# LVDS_IFC_MCX.net
KiCad netlist of a schematic drawn in Altium Designer
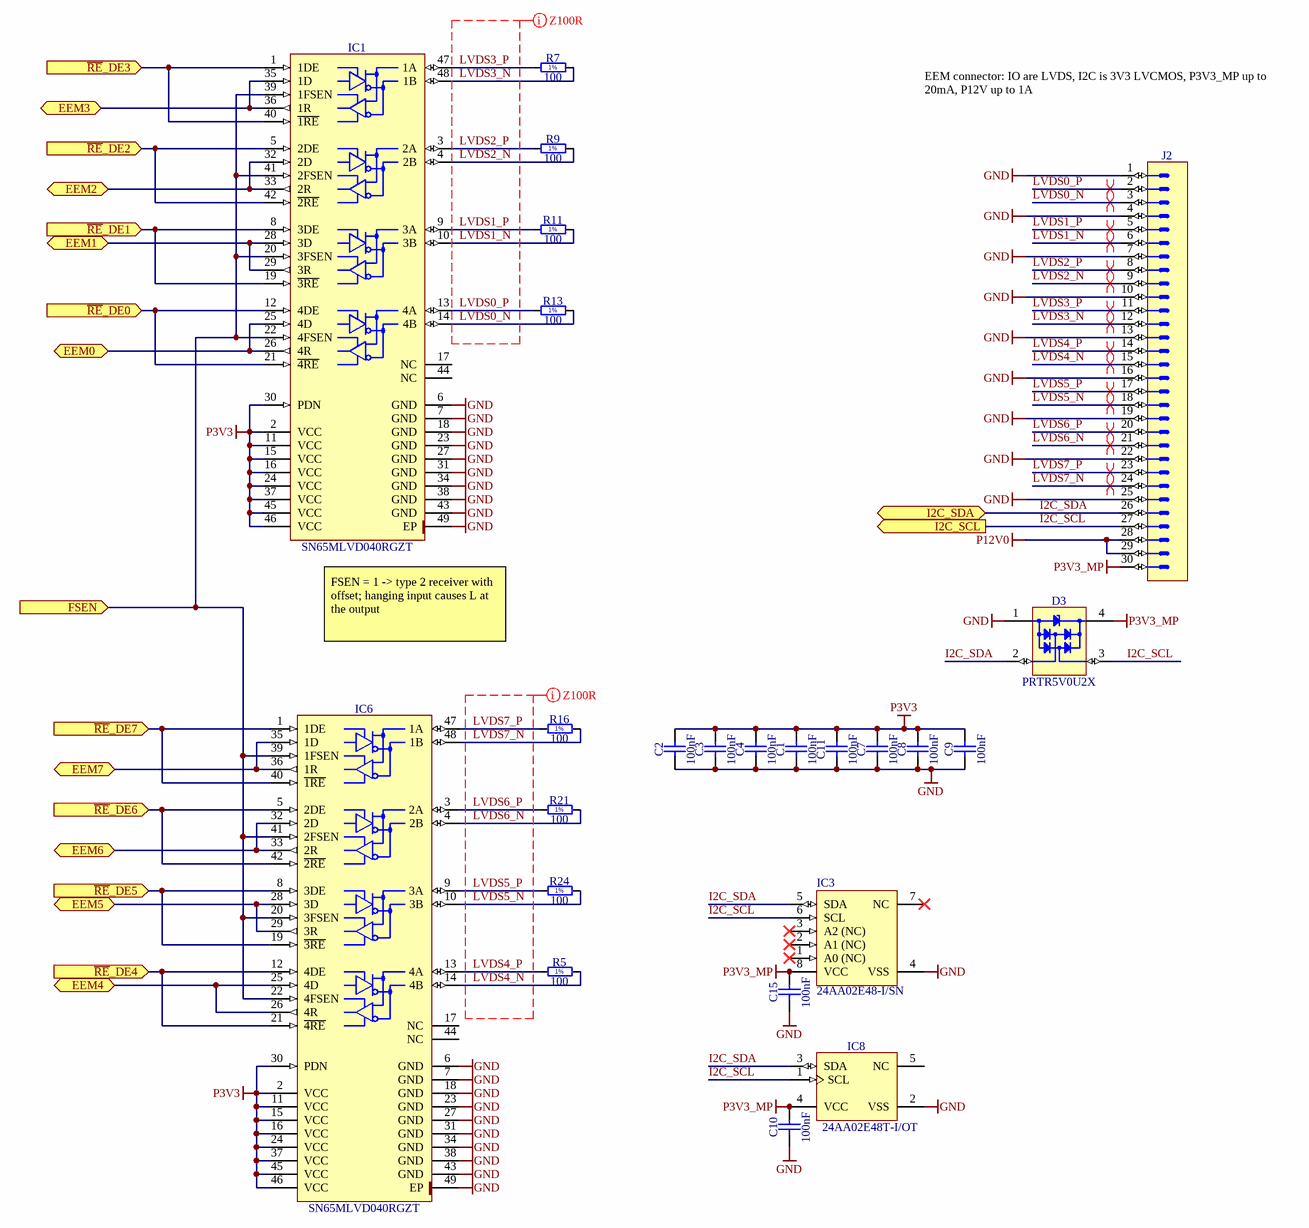
[diagram p0: LVDS_IFC_MCX.SchDoc]

(export (version "E")
  (design (tool "Eeschema 10.0.6"))
  (components
    (comp (ref "C1")
      (value "100nF")
      (footprint "CAPC1005X55N")
      (description "Non-polarised capacitor")
      (fields
        (field (name "PART NUMBER") "CC0402_100NF_16V_10%_X5R")
        (field (name "VOLTAGE") "16V")
        (field (name "AUTHOR") "CERN DEM JLC")
      )
      (libsource (lib "Capacitors") (part "Capacitor - non polarized"))
    )
    (comp (ref "C2")
      (value "100nF")
      (footprint "CAPC1005X55N")
      (description "Non-polarised capacitor")
      (fields
        (field (name "PART NUMBER") "CC0402_100NF_16V_10%_X5R")
        (field (name "VOLTAGE") "16V")
        (field (name "AUTHOR") "CERN DEM JLC")
      )
      (libsource (lib "Capacitors") (part "Capacitor - non polarized"))
    )
    (comp (ref "C3")
      (value "100nF")
      (footprint "CAPC1005X55N")
      (description "Non-polarised capacitor")
      (fields
        (field (name "PART NUMBER") "CC0402_100NF_16V_10%_X5R")
        (field (name "VOLTAGE") "16V")
        (field (name "AUTHOR") "CERN DEM JLC")
      )
      (libsource (lib "Capacitors") (part "Capacitor - non polarized"))
    )
    (comp (ref "C4")
      (value "100nF")
      (footprint "CAPC1005X55N")
      (description "Non-polarised capacitor")
      (fields
        (field (name "PART NUMBER") "CC0402_100NF_16V_10%_X5R")
        (field (name "VOLTAGE") "16V")
        (field (name "AUTHOR") "CERN DEM JLC")
      )
      (libsource (lib "Capacitors") (part "Capacitor - non polarized"))
    )
    (comp (ref "C7")
      (value "100nF")
      (footprint "CAPC1005X55N")
      (description "Non-polarised capacitor")
      (fields
        (field (name "PART NUMBER") "CC0402_100NF_16V_10%_X5R")
        (field (name "VOLTAGE") "16V")
        (field (name "AUTHOR") "CERN DEM JLC")
      )
      (libsource (lib "Capacitors") (part "Capacitor - non polarized"))
    )
    (comp (ref "C8")
      (value "100nF")
      (footprint "CAPC1005X55N")
      (description "Non-polarised capacitor")
      (fields
        (field (name "PART NUMBER") "CC0402_100NF_16V_10%_X5R")
        (field (name "VOLTAGE") "16V")
        (field (name "AUTHOR") "CERN DEM JLC")
      )
      (libsource (lib "Capacitors") (part "Capacitor - non polarized"))
    )
    (comp (ref "C9")
      (value "100nF")
      (footprint "CAPC1005X55N")
      (description "Non-polarised capacitor")
      (fields
        (field (name "PART NUMBER") "CC0402_100NF_16V_10%_X5R")
        (field (name "VOLTAGE") "16V")
        (field (name "AUTHOR") "CERN DEM JLC")
      )
      (libsource (lib "Capacitors") (part "Capacitor - non polarized"))
    )
    (comp (ref "C10")
      (value "100nF")
      (footprint "CAPC1005X55N")
      (description "Non-polarised capacitor")
      (fields
        (field (name "PART NUMBER") "CC0402_100NF_16V_10%_X5R")
        (field (name "VOLTAGE") "16V")
        (field (name "AUTHOR") "CERN DEM JLC")
      )
      (libsource (lib "Capacitors") (part "Capacitor - non polarized"))
    )
    (comp (ref "C11")
      (value "100nF")
      (footprint "CAPC1005X55N")
      (description "Non-polarised capacitor")
      (fields
        (field (name "PART NUMBER") "CC0402_100NF_16V_10%_X5R")
        (field (name "VOLTAGE") "16V")
        (field (name "AUTHOR") "CERN DEM JLC")
      )
      (libsource (lib "Capacitors") (part "Capacitor - non polarized"))
    )
    (comp (ref "C15")
      (value "100nF")
      (footprint "CAPC1005X55N")
      (description "Non-polarised capacitor")
      (fields
        (field (name "PART NUMBER") "CC0402_100NF_16V_10%_X5R")
        (field (name "VOLTAGE") "16V")
        (field (name "AUTHOR") "CERN DEM JLC")
      )
      (libsource (lib "Capacitors") (part "Capacitor - non polarized"))
    )
    (comp (ref "D3")
      (value "PRTR5V0U2X")
      (footprint "SOT190P230X110-4N")
      (description "Ultra Low Capacitance Double Rail-to-Rail ESD Protection Diode")
      (fields
        (field (name "VOLTAGE") "5.5V")
        (field (name "MANUFACTURER") "NXP SEMICONDUCTORS")
        (field (name "AUTHOR") "CERN DEM JLC")
      )
      (libsource (lib "ICs And Semiconductors") (part "PRTR5V0U2X"))
    )
    (comp (ref "IC1")
      (value "SN65MLVD040RGZT")
      (footprint "QFN50P700X700X100-49N-S420")
      (description "4-Channel Half-Duplex M-LVDS Line Transceiver")
      (fields (field (name "MANUFACTURER") "TEXAS INSTRUMENTS") (field (name "AUTHOR") "CERN DEM JLC"))
      (libsource (lib "ICs And Semiconductors") (part "SN65MLVD040"))
    )
    (comp (ref "IC3")
      (value "24AA02E48-I/SN")
      (footprint "SOIC127")
      (description "1.7V-5.5V, 2K I2C™ Serial EEPROMs with EUI-48™ Node Identity")
      (libsource (lib "Integrated_Library_MP") (part "24AA02E48-I/SN"))
    )
    (comp (ref "IC6")
      (value "SN65MLVD040RGZT")
      (footprint "QFN50P700X700X100-49N-S420")
      (description "4-Channel Half-Duplex M-LVDS Line Transceiver")
      (fields (field (name "MANUFACTURER") "TEXAS INSTRUMENTS") (field (name "AUTHOR") "CERN DEM JLC"))
      (libsource (lib "ICs And Semiconductors") (part "SN65MLVD040"))
    )
    (comp (ref "IC8")
      (value "24AA02E48T-I/OT")
      (footprint "SOT95P280X145-5N")
      (description "1.7V-5.5V, 2K I2C Serial EEPROM With EUI-48 Node Identity")
      (fields (field (name "MANUFACTURER") "MICROCHIP TECHNOLOGY") (field (name "AUTHOR") "CERN DEM MR"))
      (libsource (lib "ICs And Semiconductors") (part "24AA02E48T-I/OT"))
    )
    (comp (ref "J2")
      (value "~")
      (footprint "3M_N2530-6002RB")
      (description "Connector 30 Male")
      (fields
        (field (name "PART NUMBER") "3M_N2530-6002RB")
        (field (name "MANUFACTURER") "3M")
        (field (name "AUTHOR") "CERN DEM JLC")
      )
      (libsource (lib "Connectors") (part "Connector 30 Male"))
    )
    (comp (ref "R5")
      (value "100")
      (footprint "RESC1005X40N")
      (description "Resistor - 1%")
      (fields
        (field (name "PART NUMBER") "R0402_100R_1%_0.1W_100PPM")
        (field (name "POWER") "0.1W")
        (field (name "AUTHOR") "CERN DEM JLC")
      )
      (libsource (lib "Resistors") (part "Resistor - 1%"))
    )
    (comp (ref "R7")
      (value "100")
      (footprint "RESC1005X40N")
      (description "Resistor - 1%")
      (fields
        (field (name "PART NUMBER") "R0402_100R_1%_0.1W_100PPM")
        (field (name "POWER") "0.1W")
        (field (name "AUTHOR") "CERN DEM JLC")
      )
      (libsource (lib "Resistors") (part "Resistor - 1%"))
    )
    (comp (ref "R9")
      (value "100")
      (footprint "RESC1005X40N")
      (description "Resistor - 1%")
      (fields
        (field (name "PART NUMBER") "R0402_100R_1%_0.1W_100PPM")
        (field (name "POWER") "0.1W")
        (field (name "AUTHOR") "CERN DEM JLC")
      )
      (libsource (lib "Resistors") (part "Resistor - 1%"))
    )
    (comp (ref "R11")
      (value "100")
      (footprint "RESC1005X40N")
      (description "Resistor - 1%")
      (fields
        (field (name "PART NUMBER") "R0402_100R_1%_0.1W_100PPM")
        (field (name "POWER") "0.1W")
        (field (name "AUTHOR") "CERN DEM JLC")
      )
      (libsource (lib "Resistors") (part "Resistor - 1%"))
    )
    (comp (ref "R13")
      (value "100")
      (footprint "RESC1005X40N")
      (description "Resistor - 1%")
      (fields
        (field (name "PART NUMBER") "R0402_100R_1%_0.1W_100PPM")
        (field (name "POWER") "0.1W")
        (field (name "AUTHOR") "CERN DEM JLC")
      )
      (libsource (lib "Resistors") (part "Resistor - 1%"))
    )
    (comp (ref "R16")
      (value "100")
      (footprint "RESC1005X40N")
      (description "Resistor - 1%")
      (fields
        (field (name "PART NUMBER") "R0402_100R_1%_0.1W_100PPM")
        (field (name "POWER") "0.1W")
        (field (name "AUTHOR") "CERN DEM JLC")
      )
      (libsource (lib "Resistors") (part "Resistor - 1%"))
    )
    (comp (ref "R21")
      (value "100")
      (footprint "RESC1005X40N")
      (description "Resistor - 1%")
      (fields
        (field (name "PART NUMBER") "R0402_100R_1%_0.1W_100PPM")
        (field (name "POWER") "0.1W")
        (field (name "AUTHOR") "CERN DEM JLC")
      )
      (libsource (lib "Resistors") (part "Resistor - 1%"))
    )
    (comp (ref "R24")
      (value "100")
      (footprint "RESC1005X40N")
      (description "Resistor - 1%")
      (fields
        (field (name "PART NUMBER") "R0402_100R_1%_0.1W_100PPM")
        (field (name "POWER") "0.1W")
        (field (name "AUTHOR") "CERN DEM JLC")
      )
      (libsource (lib "Resistors") (part "Resistor - 1%"))
    )
  )
  (nets
    (net (code "1") (name "/EEM0") (class "Default")
      (node (ref "IC1") (pin "25") (pinfunction "4D_25") (pintype "input"))
      (node (ref "IC1") (pin "26") (pinfunction "4R_26") (pintype "output"))
    )
    (net (code "2") (name "/EEM1") (class "Default")
      (node (ref "IC1") (pin "28") (pinfunction "3D_28") (pintype "input"))
      (node (ref "IC1") (pin "29") (pinfunction "3R_29") (pintype "output"))
    )
    (net (code "3") (name "/EEM2") (class "Default")
      (node (ref "IC1") (pin "32") (pinfunction "2D_32") (pintype "input"))
      (node (ref "IC1") (pin "33") (pinfunction "2R_33") (pintype "output"))
    )
    (net (code "4") (name "/EEM3") (class "Default")
      (node (ref "IC1") (pin "35") (pinfunction "1D_35") (pintype "input"))
      (node (ref "IC1") (pin "36") (pinfunction "1R_36") (pintype "output"))
    )
    (net (code "5") (name "/EEM4") (class "Default")
      (node (ref "IC6") (pin "25") (pinfunction "4D_25") (pintype "input"))
      (node (ref "IC6") (pin "26") (pinfunction "4R_26") (pintype "output"))
    )
    (net (code "6") (name "/EEM5") (class "Default")
      (node (ref "IC6") (pin "28") (pinfunction "3D_28") (pintype "input"))
      (node (ref "IC6") (pin "29") (pinfunction "3R_29") (pintype "output"))
    )
    (net (code "7") (name "/EEM6") (class "Default")
      (node (ref "IC6") (pin "32") (pinfunction "2D_32") (pintype "input"))
      (node (ref "IC6") (pin "33") (pinfunction "2R_33") (pintype "output"))
    )
    (net (code "8") (name "/EEM7") (class "Default")
      (node (ref "IC6") (pin "35") (pinfunction "1D_35") (pintype "input"))
      (node (ref "IC6") (pin "36") (pinfunction "1R_36") (pintype "output"))
    )
    (net (code "9") (name "/FSEN") (class "Default")
      (node (ref "IC1") (pin "20") (pinfunction "3FSEN_20") (pintype "input"))
      (node (ref "IC1") (pin "22") (pinfunction "4FSEN_22") (pintype "input"))
      (node (ref "IC1") (pin "39") (pinfunction "1FSEN_39") (pintype "input"))
      (node (ref "IC1") (pin "41") (pinfunction "2FSEN_41") (pintype "input"))
      (node (ref "IC6") (pin "20") (pinfunction "3FSEN_20") (pintype "input"))
      (node (ref "IC6") (pin "22") (pinfunction "4FSEN_22") (pintype "input"))
      (node (ref "IC6") (pin "39") (pinfunction "1FSEN_39") (pintype "input"))
      (node (ref "IC6") (pin "41") (pinfunction "2FSEN_41") (pintype "input"))
    )
    (net (code "10") (name "/I2C_SCL") (class "Default")
      (node (ref "D3") (pin "3") (pinfunction "I/O2_3") (pintype "bidirectional"))
      (node (ref "IC3") (pin "6") (pinfunction "SCL_6") (pintype "input"))
      (node (ref "IC8") (pin "1") (pinfunction "SCL_1") (pintype "input"))
      (node (ref "J2") (pin "27") (pinfunction "27_27") (pintype "bidirectional"))
    )
    (net (code "11") (name "/I2C_SDA") (class "Default")
      (node (ref "D3") (pin "2") (pinfunction "I/O1_2") (pintype "bidirectional"))
      (node (ref "IC3") (pin "5") (pinfunction "SDA_5") (pintype "bidirectional"))
      (node (ref "IC8") (pin "3") (pinfunction "SDA_3") (pintype "bidirectional"))
      (node (ref "J2") (pin "26") (pinfunction "26_26") (pintype "bidirectional"))
    )
    (net (code "12") (name "/LVDS0_N") (class "Default")
      (node (ref "IC1") (pin "14") (pinfunction "4B_14") (pintype "bidirectional"))
      (node (ref "J2") (pin "3") (pinfunction "3_3") (pintype "bidirectional"))
      (node (ref "R13") (pin "2") (pinfunction "2_2") (pintype "passive"))
    )
    (net (code "13") (name "/LVDS0_P") (class "Default")
      (node (ref "IC1") (pin "13") (pinfunction "4A_13") (pintype "bidirectional"))
      (node (ref "J2") (pin "2") (pinfunction "2_2") (pintype "bidirectional"))
      (node (ref "R13") (pin "1") (pinfunction "1_1") (pintype "passive"))
    )
    (net (code "14") (name "/LVDS1_N") (class "Default")
      (node (ref "IC1") (pin "10") (pinfunction "3B_10") (pintype "bidirectional"))
      (node (ref "J2") (pin "6") (pinfunction "6_6") (pintype "bidirectional"))
      (node (ref "R11") (pin "2") (pinfunction "2_2") (pintype "passive"))
    )
    (net (code "15") (name "/LVDS1_P") (class "Default")
      (node (ref "IC1") (pin "9") (pinfunction "3A_9") (pintype "bidirectional"))
      (node (ref "J2") (pin "5") (pinfunction "5_5") (pintype "bidirectional"))
      (node (ref "R11") (pin "1") (pinfunction "1_1") (pintype "passive"))
    )
    (net (code "16") (name "/LVDS2_N") (class "Default")
      (node (ref "IC1") (pin "4") (pinfunction "2B_4") (pintype "bidirectional"))
      (node (ref "J2") (pin "9") (pinfunction "9_9") (pintype "bidirectional"))
      (node (ref "R9") (pin "2") (pinfunction "2_2") (pintype "passive"))
    )
    (net (code "17") (name "/LVDS2_P") (class "Default")
      (node (ref "IC1") (pin "3") (pinfunction "2A_3") (pintype "bidirectional"))
      (node (ref "J2") (pin "8") (pinfunction "8_8") (pintype "bidirectional"))
      (node (ref "R9") (pin "1") (pinfunction "1_1") (pintype "passive"))
    )
    (net (code "18") (name "/LVDS3_N") (class "Default")
      (node (ref "IC1") (pin "48") (pinfunction "1B_48") (pintype "bidirectional"))
      (node (ref "J2") (pin "12") (pinfunction "12_12") (pintype "bidirectional"))
      (node (ref "R7") (pin "2") (pinfunction "2_2") (pintype "passive"))
    )
    (net (code "19") (name "/LVDS3_P") (class "Default")
      (node (ref "IC1") (pin "47") (pinfunction "1A_47") (pintype "bidirectional"))
      (node (ref "J2") (pin "11") (pinfunction "11_11") (pintype "bidirectional"))
      (node (ref "R7") (pin "1") (pinfunction "1_1") (pintype "passive"))
    )
    (net (code "20") (name "/LVDS4_N") (class "Default")
      (node (ref "IC6") (pin "14") (pinfunction "4B_14") (pintype "bidirectional"))
      (node (ref "J2") (pin "15") (pinfunction "15_15") (pintype "bidirectional"))
      (node (ref "R5") (pin "2") (pinfunction "2_2") (pintype "passive"))
    )
    (net (code "21") (name "/LVDS4_P") (class "Default")
      (node (ref "IC6") (pin "13") (pinfunction "4A_13") (pintype "bidirectional"))
      (node (ref "J2") (pin "14") (pinfunction "14_14") (pintype "bidirectional"))
      (node (ref "R5") (pin "1") (pinfunction "1_1") (pintype "passive"))
    )
    (net (code "22") (name "/LVDS5_N") (class "Default")
      (node (ref "IC6") (pin "10") (pinfunction "3B_10") (pintype "bidirectional"))
      (node (ref "J2") (pin "18") (pinfunction "18_18") (pintype "bidirectional"))
      (node (ref "R24") (pin "2") (pinfunction "2_2") (pintype "passive"))
    )
    (net (code "23") (name "/LVDS5_P") (class "Default")
      (node (ref "IC6") (pin "9") (pinfunction "3A_9") (pintype "bidirectional"))
      (node (ref "J2") (pin "17") (pinfunction "17_17") (pintype "bidirectional"))
      (node (ref "R24") (pin "1") (pinfunction "1_1") (pintype "passive"))
    )
    (net (code "24") (name "/LVDS6_N") (class "Default")
      (node (ref "IC6") (pin "4") (pinfunction "2B_4") (pintype "bidirectional"))
      (node (ref "J2") (pin "21") (pinfunction "21_21") (pintype "bidirectional"))
      (node (ref "R21") (pin "2") (pinfunction "2_2") (pintype "passive"))
    )
    (net (code "25") (name "/LVDS6_P") (class "Default")
      (node (ref "IC6") (pin "3") (pinfunction "2A_3") (pintype "bidirectional"))
      (node (ref "J2") (pin "20") (pinfunction "20_20") (pintype "bidirectional"))
      (node (ref "R21") (pin "1") (pinfunction "1_1") (pintype "passive"))
    )
    (net (code "26") (name "/LVDS7_N") (class "Default")
      (node (ref "IC6") (pin "48") (pinfunction "1B_48") (pintype "bidirectional"))
      (node (ref "J2") (pin "24") (pinfunction "24_24") (pintype "bidirectional"))
      (node (ref "R16") (pin "2") (pinfunction "2_2") (pintype "passive"))
    )
    (net (code "27") (name "/LVDS7_P") (class "Default")
      (node (ref "IC6") (pin "47") (pinfunction "1A_47") (pintype "bidirectional"))
      (node (ref "J2") (pin "23") (pinfunction "23_23") (pintype "bidirectional"))
      (node (ref "R16") (pin "1") (pinfunction "1_1") (pintype "passive"))
    )
    (net (code "28") (name "/~{RE}_DE0") (class "Default")
      (node (ref "IC1") (pin "12") (pinfunction "4DE_12") (pintype "input"))
      (node (ref "IC1") (pin "21") (pinfunction "~{4RE}_21") (pintype "input"))
    )
    (net (code "29") (name "/~{RE}_DE1") (class "Default")
      (node (ref "IC1") (pin "19") (pinfunction "~{3RE}_19") (pintype "input"))
      (node (ref "IC1") (pin "8") (pinfunction "3DE_8") (pintype "input"))
    )
    (net (code "30") (name "/~{RE}_DE2") (class "Default")
      (node (ref "IC1") (pin "42") (pinfunction "~{2RE}_42") (pintype "input"))
      (node (ref "IC1") (pin "5") (pinfunction "2DE_5") (pintype "input"))
    )
    (net (code "31") (name "/~{RE}_DE3") (class "Default")
      (node (ref "IC1") (pin "1") (pinfunction "1DE_1") (pintype "input"))
      (node (ref "IC1") (pin "40") (pinfunction "~{1RE}_40") (pintype "input"))
    )
    (net (code "32") (name "/~{RE}_DE4") (class "Default")
      (node (ref "IC6") (pin "12") (pinfunction "4DE_12") (pintype "input"))
      (node (ref "IC6") (pin "21") (pinfunction "~{4RE}_21") (pintype "input"))
    )
    (net (code "33") (name "/~{RE}_DE5") (class "Default")
      (node (ref "IC6") (pin "19") (pinfunction "~{3RE}_19") (pintype "input"))
      (node (ref "IC6") (pin "8") (pinfunction "3DE_8") (pintype "input"))
    )
    (net (code "34") (name "/~{RE}_DE6") (class "Default")
      (node (ref "IC6") (pin "42") (pinfunction "~{2RE}_42") (pintype "input"))
      (node (ref "IC6") (pin "5") (pinfunction "2DE_5") (pintype "input"))
    )
    (net (code "35") (name "/~{RE}_DE7") (class "Default")
      (node (ref "IC6") (pin "1") (pinfunction "1DE_1") (pintype "input"))
      (node (ref "IC6") (pin "40") (pinfunction "~{1RE}_40") (pintype "input"))
    )
    (net (code "36") (name "GND") (class "Default")
      (node (ref "C1") (pin "1") (pinfunction "1_1") (pintype "passive"))
      (node (ref "C10") (pin "1") (pinfunction "1_1") (pintype "passive"))
      (node (ref "C11") (pin "1") (pinfunction "1_1") (pintype "passive"))
      (node (ref "C15") (pin "1") (pinfunction "1_1") (pintype "passive"))
      (node (ref "C2") (pin "1") (pinfunction "1_1") (pintype "passive"))
      (node (ref "C3") (pin "1") (pinfunction "1_1") (pintype "passive"))
      (node (ref "C4") (pin "1") (pinfunction "1_1") (pintype "passive"))
      (node (ref "C7") (pin "1") (pinfunction "1_1") (pintype "passive"))
      (node (ref "C8") (pin "1") (pinfunction "1_1") (pintype "passive"))
      (node (ref "C9") (pin "1") (pinfunction "1_1") (pintype "passive"))
      (node (ref "D3") (pin "1") (pinfunction "GND_1") (pintype "power_in"))
      (node (ref "IC1") (pin "18") (pinfunction "GND_18") (pintype "power_in"))
      (node (ref "IC1") (pin "23") (pinfunction "GND_23") (pintype "power_in"))
      (node (ref "IC1") (pin "27") (pinfunction "GND_27") (pintype "power_in"))
      (node (ref "IC1") (pin "31") (pinfunction "GND_31") (pintype "power_in"))
      (node (ref "IC1") (pin "34") (pinfunction "GND_34") (pintype "power_in"))
      (node (ref "IC1") (pin "38") (pinfunction "GND_38") (pintype "power_in"))
      (node (ref "IC1") (pin "43") (pinfunction "GND_43") (pintype "power_in"))
      (node (ref "IC1") (pin "49") (pinfunction "EP_49") (pintype "power_in"))
      (node (ref "IC1") (pin "6") (pinfunction "GND_6") (pintype "power_in"))
      (node (ref "IC1") (pin "7") (pinfunction "GND_7") (pintype "power_in"))
      (node (ref "IC3") (pin "4") (pinfunction "VSS_4") (pintype "passive"))
      (node (ref "IC6") (pin "18") (pinfunction "GND_18") (pintype "power_in"))
      (node (ref "IC6") (pin "23") (pinfunction "GND_23") (pintype "power_in"))
      (node (ref "IC6") (pin "27") (pinfunction "GND_27") (pintype "power_in"))
      (node (ref "IC6") (pin "31") (pinfunction "GND_31") (pintype "power_in"))
      (node (ref "IC6") (pin "34") (pinfunction "GND_34") (pintype "power_in"))
      (node (ref "IC6") (pin "38") (pinfunction "GND_38") (pintype "power_in"))
      (node (ref "IC6") (pin "43") (pinfunction "GND_43") (pintype "power_in"))
      (node (ref "IC6") (pin "49") (pinfunction "EP_49") (pintype "power_in"))
      (node (ref "IC6") (pin "6") (pinfunction "GND_6") (pintype "power_in"))
      (node (ref "IC6") (pin "7") (pinfunction "GND_7") (pintype "power_in"))
      (node (ref "IC8") (pin "2") (pinfunction "VSS_2") (pintype "power_in"))
      (node (ref "J2") (pin "1") (pinfunction "1_1") (pintype "bidirectional"))
      (node (ref "J2") (pin "10") (pinfunction "10_10") (pintype "bidirectional"))
      (node (ref "J2") (pin "13") (pinfunction "13_13") (pintype "bidirectional"))
      (node (ref "J2") (pin "16") (pinfunction "16_16") (pintype "bidirectional"))
      (node (ref "J2") (pin "19") (pinfunction "19_19") (pintype "bidirectional"))
      (node (ref "J2") (pin "22") (pinfunction "22_22") (pintype "bidirectional"))
      (node (ref "J2") (pin "25") (pinfunction "25_25") (pintype "bidirectional"))
      (node (ref "J2") (pin "4") (pinfunction "4_4") (pintype "bidirectional"))
      (node (ref "J2") (pin "7") (pinfunction "7_7") (pintype "bidirectional"))
    )
    (net (code "37") (name "P3V3") (class "Default")
      (node (ref "C1") (pin "2") (pinfunction "2_2") (pintype "passive"))
      (node (ref "C11") (pin "2") (pinfunction "2_2") (pintype "passive"))
      (node (ref "C2") (pin "2") (pinfunction "2_2") (pintype "passive"))
      (node (ref "C3") (pin "2") (pinfunction "2_2") (pintype "passive"))
      (node (ref "C4") (pin "2") (pinfunction "2_2") (pintype "passive"))
      (node (ref "C7") (pin "2") (pinfunction "2_2") (pintype "passive"))
      (node (ref "C8") (pin "2") (pinfunction "2_2") (pintype "passive"))
      (node (ref "C9") (pin "2") (pinfunction "2_2") (pintype "passive"))
      (node (ref "IC1") (pin "11") (pinfunction "VCC_11") (pintype "power_in"))
      (node (ref "IC1") (pin "15") (pinfunction "VCC_15") (pintype "power_in"))
      (node (ref "IC1") (pin "16") (pinfunction "VCC_16") (pintype "power_in"))
      (node (ref "IC1") (pin "2") (pinfunction "VCC_2") (pintype "power_in"))
      (node (ref "IC1") (pin "24") (pinfunction "VCC_24") (pintype "power_in"))
      (node (ref "IC1") (pin "30") (pinfunction "PDN_30") (pintype "input"))
      (node (ref "IC1") (pin "37") (pinfunction "VCC_37") (pintype "power_in"))
      (node (ref "IC1") (pin "45") (pinfunction "VCC_45") (pintype "power_in"))
      (node (ref "IC1") (pin "46") (pinfunction "VCC_46") (pintype "power_in"))
      (node (ref "IC6") (pin "11") (pinfunction "VCC_11") (pintype "power_in"))
      (node (ref "IC6") (pin "15") (pinfunction "VCC_15") (pintype "power_in"))
      (node (ref "IC6") (pin "16") (pinfunction "VCC_16") (pintype "power_in"))
      (node (ref "IC6") (pin "2") (pinfunction "VCC_2") (pintype "power_in"))
      (node (ref "IC6") (pin "24") (pinfunction "VCC_24") (pintype "power_in"))
      (node (ref "IC6") (pin "30") (pinfunction "PDN_30") (pintype "input"))
      (node (ref "IC6") (pin "37") (pinfunction "VCC_37") (pintype "power_in"))
      (node (ref "IC6") (pin "45") (pinfunction "VCC_45") (pintype "power_in"))
      (node (ref "IC6") (pin "46") (pinfunction "VCC_46") (pintype "power_in"))
    )
    (net (code "38") (name "P3V3_MP") (class "Default")
      (node (ref "C10") (pin "2") (pinfunction "2_2") (pintype "passive"))
      (node (ref "C15") (pin "2") (pinfunction "2_2") (pintype "passive"))
      (node (ref "D3") (pin "4") (pinfunction "VCC_4") (pintype "power_in"))
      (node (ref "IC3") (pin "8") (pinfunction "VCC_8") (pintype "passive"))
      (node (ref "IC8") (pin "4") (pinfunction "VCC_4") (pintype "power_in"))
      (node (ref "J2") (pin "30") (pinfunction "30_30") (pintype "bidirectional"))
    )
    (net (code "39") (name "P12V0") (class "Default")
      (node (ref "J2") (pin "28") (pinfunction "28_28") (pintype "bidirectional"))
      (node (ref "J2") (pin "29") (pinfunction "29_29") (pintype "bidirectional"))
    )
    (net (code "40") (name "unconnected-(IC1-NC-Pad17)") (class "Default")
      (node (ref "IC1") (pin "17") (pinfunction "NC_17") (pintype "passive"))
    )
    (net (code "41") (name "unconnected-(IC1-NC-Pad44)") (class "Default")
      (node (ref "IC1") (pin "44") (pinfunction "NC_44") (pintype "passive"))
    )
    (net (code "42") (name "unconnected-(IC3-A0_(NC)-Pad1)") (class "Default")
      (node (ref "IC3") (pin "1") (pinfunction "A0_(NC)_1") (pintype "input+no_connect"))
    )
    (net (code "43") (name "unconnected-(IC3-A1_(NC)-Pad2)") (class "Default")
      (node (ref "IC3") (pin "2") (pinfunction "A1_(NC)_2") (pintype "input+no_connect"))
    )
    (net (code "44") (name "unconnected-(IC3-A2_(NC)-Pad3)") (class "Default")
      (node (ref "IC3") (pin "3") (pinfunction "A2_(NC)_3") (pintype "input+no_connect"))
    )
    (net (code "45") (name "unconnected-(IC3-NC-Pad7)") (class "Default")
      (node (ref "IC3") (pin "7") (pinfunction "NC_7") (pintype "passive+no_connect"))
    )
    (net (code "46") (name "unconnected-(IC6-NC-Pad17)") (class "Default")
      (node (ref "IC6") (pin "17") (pinfunction "NC_17") (pintype "passive"))
    )
    (net (code "47") (name "unconnected-(IC6-NC-Pad44)") (class "Default")
      (node (ref "IC6") (pin "44") (pinfunction "NC_44") (pintype "passive"))
    )
    (net (code "48") (name "unconnected-(IC8-NC-Pad5)") (class "Default")
      (node (ref "IC8") (pin "5") (pinfunction "NC_5") (pintype "passive"))
    )
  )
)
